# Rocky_Switch_Shield.net
KiCad netlist of a schematic drawn in EAGLE
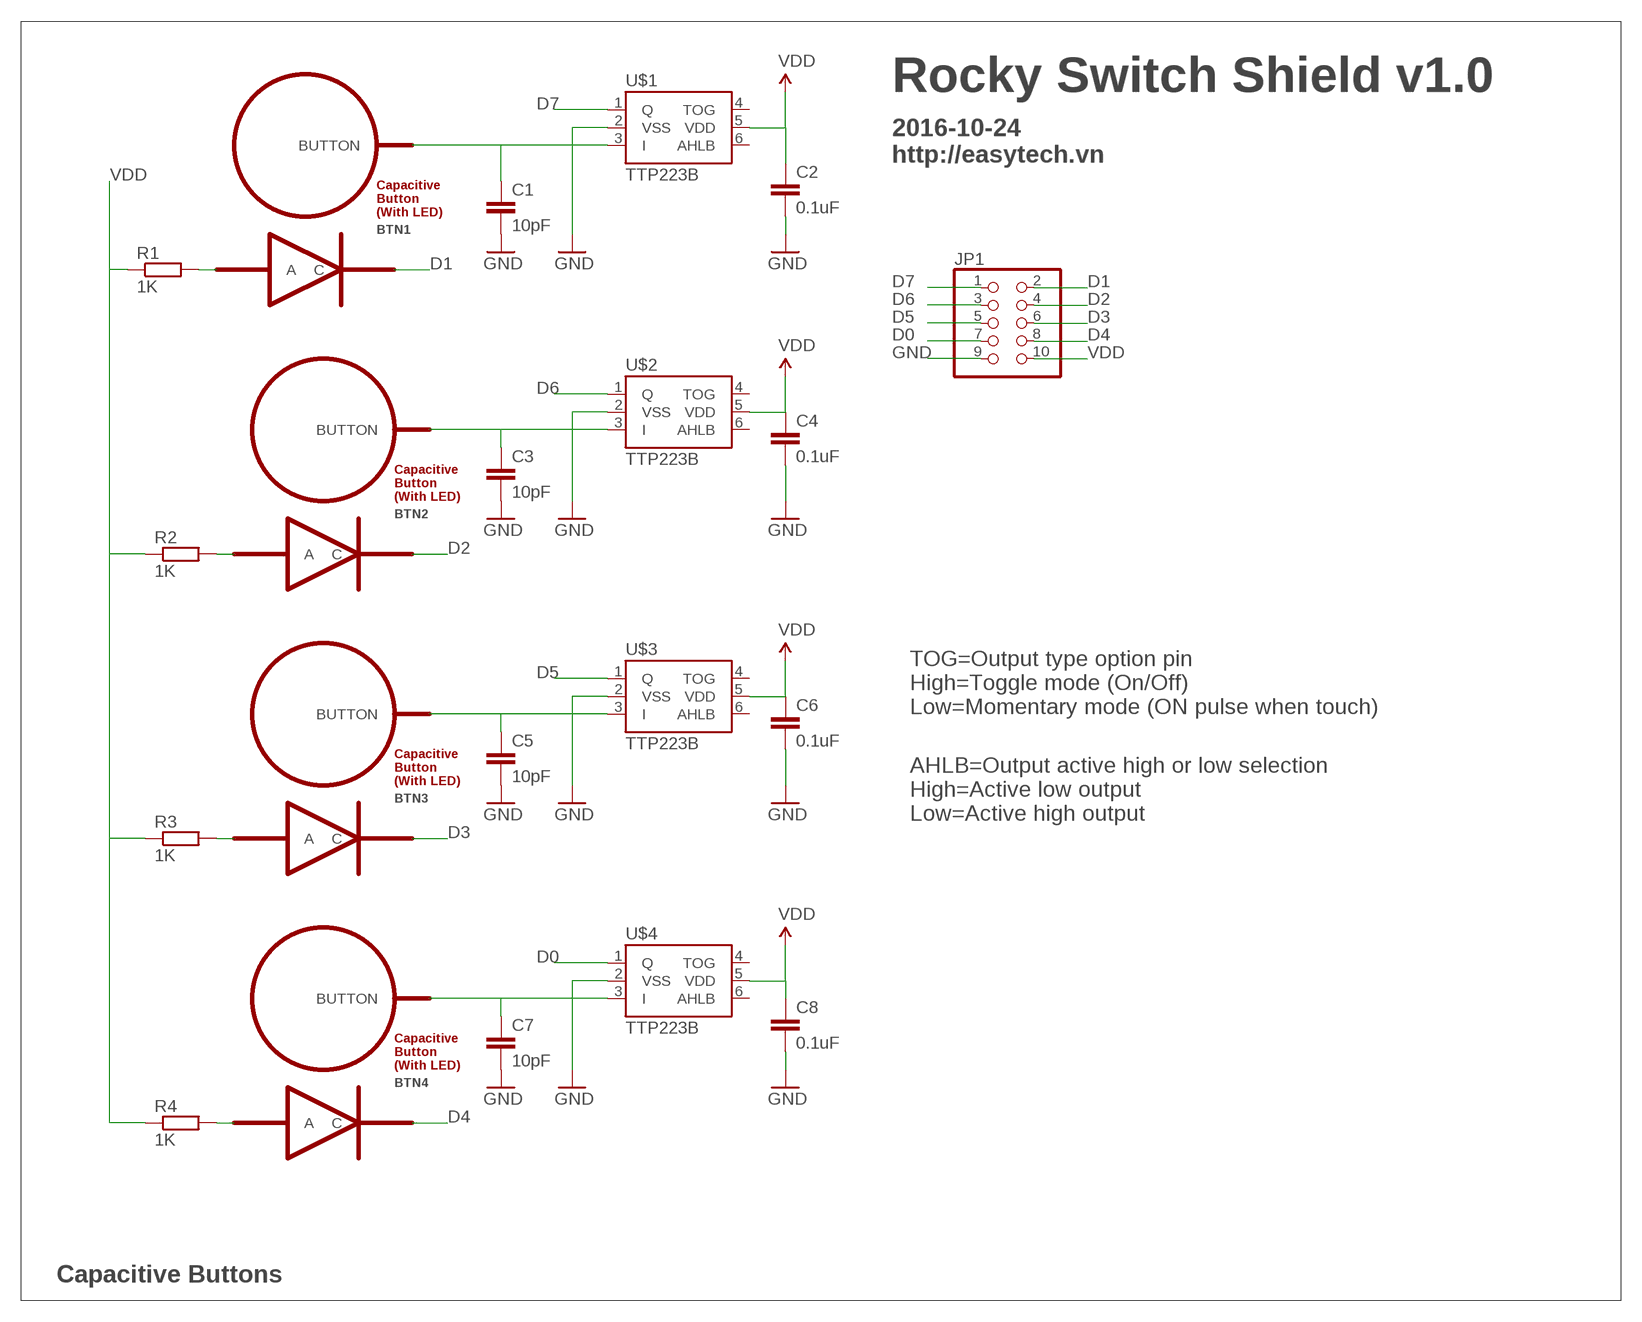
[diagram p0: schematic, sheet 1]

(export (version "E")
  (design (tool "Eeschema 10.0.6"))
  (components
    (comp (ref "BTN1")
      (value "BUTTON_PASSIVE_LED")
      (footprint "eagle-import:BUTTON_PASSIVE_LED")
      (libsource (lib "eagle-import") (part "BUTTON_PASSIVE_LED"))
    )
    (comp (ref "BTN2")
      (value "BUTTON_PASSIVE_LED")
      (footprint "eagle-import:BUTTON_PASSIVE_LED")
      (libsource (lib "eagle-import") (part "BUTTON_PASSIVE_LED"))
    )
    (comp (ref "BTN3")
      (value "BUTTON_PASSIVE_LED")
      (footprint "eagle-import:BUTTON_PASSIVE_LED")
      (libsource (lib "eagle-import") (part "BUTTON_PASSIVE_LED"))
    )
    (comp (ref "BTN4")
      (value "BUTTON_PASSIVE_LED")
      (footprint "eagle-import:BUTTON_PASSIVE_LED")
      (libsource (lib "eagle-import") (part "BUTTON_PASSIVE_LED"))
    )
    (comp (ref "C1")
      (value "10pF")
      (footprint "eagle-import:C0805K")
      (libsource (lib "eagle-import") (part "C-EUC0805K"))
    )
    (comp (ref "C2")
      (value "0.1uF")
      (footprint "eagle-import:C0805K")
      (libsource (lib "eagle-import") (part "C-EUC0805K"))
    )
    (comp (ref "C3")
      (value "10pF")
      (footprint "eagle-import:C0805K")
      (libsource (lib "eagle-import") (part "C-EUC0805K"))
    )
    (comp (ref "C4")
      (value "0.1uF")
      (footprint "eagle-import:C0805K")
      (libsource (lib "eagle-import") (part "C-EUC0805K"))
    )
    (comp (ref "C5")
      (value "10pF")
      (footprint "eagle-import:C0805K")
      (libsource (lib "eagle-import") (part "C-EUC0805K"))
    )
    (comp (ref "C6")
      (value "0.1uF")
      (footprint "eagle-import:C0805K")
      (libsource (lib "eagle-import") (part "C-EUC0805K"))
    )
    (comp (ref "C7")
      (value "10pF")
      (footprint "eagle-import:C0805K")
      (libsource (lib "eagle-import") (part "C-EUC0805K"))
    )
    (comp (ref "C8")
      (value "0.1uF")
      (footprint "eagle-import:C0805K")
      (libsource (lib "eagle-import") (part "C-EUC0805K"))
    )
    (comp (ref "JP1")
      (value "PINHD-2X5")
      (footprint "eagle-import:2X05")
      (libsource (lib "eagle-import") (part "PINHD-2X5"))
    )
    (comp (ref "R1")
      (value "1K")
      (footprint "eagle-import:R0805")
      (libsource (lib "eagle-import") (part "R-EU_R0805"))
    )
    (comp (ref "R2")
      (value "1K")
      (footprint "eagle-import:R0805")
      (libsource (lib "eagle-import") (part "R-EU_R0805"))
    )
    (comp (ref "R3")
      (value "1K")
      (footprint "eagle-import:R0805")
      (libsource (lib "eagle-import") (part "R-EU_R0805"))
    )
    (comp (ref "R4")
      (value "1K")
      (footprint "eagle-import:R0805")
      (libsource (lib "eagle-import") (part "R-EU_R0805"))
    )
    (comp (ref "U$1")
      (value "TTP223B")
      (footprint "eagle-import:SOT23-6")
      (libsource (lib "eagle-import") (part "TTP223B"))
    )
    (comp (ref "U$2")
      (value "TTP223B")
      (footprint "eagle-import:SOT23-6")
      (libsource (lib "eagle-import") (part "TTP223B"))
    )
    (comp (ref "U$3")
      (value "TTP223B")
      (footprint "eagle-import:SOT23-6")
      (libsource (lib "eagle-import") (part "TTP223B"))
    )
    (comp (ref "U$4")
      (value "TTP223B")
      (footprint "eagle-import:SOT23-6")
      (libsource (lib "eagle-import") (part "TTP223B"))
    )
  )
  (nets
    (net (code "1") (name "/D0") (class "Default")
      (node (ref "JP1") (pin "7") (pinfunction "7_7") (pintype "passive"))
      (node (ref "U$4") (pin "1") (pinfunction "Q_1") (pintype "bidirectional"))
    )
    (net (code "2") (name "/D1") (class "Default")
      (node (ref "BTN1") (pin "C") (pinfunction "C_C") (pintype "bidirectional"))
      (node (ref "JP1") (pin "2") (pinfunction "2_2") (pintype "passive"))
    )
    (net (code "3") (name "/D2") (class "Default")
      (node (ref "BTN2") (pin "C") (pinfunction "C_C") (pintype "bidirectional"))
      (node (ref "JP1") (pin "4") (pinfunction "4_4") (pintype "passive"))
    )
    (net (code "4") (name "/D3") (class "Default")
      (node (ref "BTN3") (pin "C") (pinfunction "C_C") (pintype "bidirectional"))
      (node (ref "JP1") (pin "6") (pinfunction "6_6") (pintype "passive"))
    )
    (net (code "5") (name "/D4") (class "Default")
      (node (ref "BTN4") (pin "C") (pinfunction "C_C") (pintype "bidirectional"))
      (node (ref "JP1") (pin "8") (pinfunction "8_8") (pintype "passive"))
    )
    (net (code "6") (name "/D5") (class "Default")
      (node (ref "JP1") (pin "5") (pinfunction "5_5") (pintype "passive"))
      (node (ref "U$3") (pin "1") (pinfunction "Q_1") (pintype "bidirectional"))
    )
    (net (code "7") (name "/D6") (class "Default")
      (node (ref "JP1") (pin "3") (pinfunction "3_3") (pintype "passive"))
      (node (ref "U$2") (pin "1") (pinfunction "Q_1") (pintype "bidirectional"))
    )
    (net (code "8") (name "/D7") (class "Default")
      (node (ref "JP1") (pin "1") (pinfunction "1_1") (pintype "passive"))
      (node (ref "U$1") (pin "1") (pinfunction "Q_1") (pintype "bidirectional"))
    )
    (net (code "9") (name "GND") (class "Default")
      (node (ref "C1") (pin "2") (pinfunction "2_2") (pintype "passive"))
      (node (ref "C2") (pin "2") (pinfunction "2_2") (pintype "passive"))
      (node (ref "C3") (pin "2") (pinfunction "2_2") (pintype "passive"))
      (node (ref "C4") (pin "2") (pinfunction "2_2") (pintype "passive"))
      (node (ref "C5") (pin "2") (pinfunction "2_2") (pintype "passive"))
      (node (ref "C6") (pin "2") (pinfunction "2_2") (pintype "passive"))
      (node (ref "C7") (pin "2") (pinfunction "2_2") (pintype "passive"))
      (node (ref "C8") (pin "2") (pinfunction "2_2") (pintype "passive"))
      (node (ref "JP1") (pin "9") (pinfunction "9_9") (pintype "passive"))
      (node (ref "U$1") (pin "2") (pinfunction "VSS_2") (pintype "bidirectional"))
      (node (ref "U$2") (pin "2") (pinfunction "VSS_2") (pintype "bidirectional"))
      (node (ref "U$3") (pin "2") (pinfunction "VSS_2") (pintype "bidirectional"))
      (node (ref "U$4") (pin "2") (pinfunction "VSS_2") (pintype "bidirectional"))
    )
    (net (code "10") (name "Net-(BTN1-PadA)") (class "Default")
      (node (ref "BTN1") (pin "A") (pinfunction "A_A") (pintype "bidirectional"))
      (node (ref "R1") (pin "2") (pinfunction "2_2") (pintype "passive"))
    )
    (net (code "11") (name "Net-(BTN2-PadA)") (class "Default")
      (node (ref "BTN2") (pin "A") (pinfunction "A_A") (pintype "bidirectional"))
      (node (ref "R2") (pin "2") (pinfunction "2_2") (pintype "passive"))
    )
    (net (code "12") (name "Net-(BTN3-PadA)") (class "Default")
      (node (ref "BTN3") (pin "A") (pinfunction "A_A") (pintype "bidirectional"))
      (node (ref "R3") (pin "2") (pinfunction "2_2") (pintype "passive"))
    )
    (net (code "13") (name "Net-(BTN4-PadA)") (class "Default")
      (node (ref "BTN4") (pin "A") (pinfunction "A_A") (pintype "bidirectional"))
      (node (ref "R4") (pin "2") (pinfunction "2_2") (pintype "passive"))
    )
    (net (code "14") (name "Net-(U$1-I)") (class "Default")
      (node (ref "BTN1") (pin "BUTTON") (pinfunction "BUTTON_BUTTON") (pintype "passive"))
      (node (ref "C1") (pin "1") (pinfunction "1_1") (pintype "passive"))
      (node (ref "U$1") (pin "3") (pinfunction "I_3") (pintype "bidirectional"))
    )
    (net (code "15") (name "Net-(U$2-I)") (class "Default")
      (node (ref "BTN2") (pin "BUTTON") (pinfunction "BUTTON_BUTTON") (pintype "passive"))
      (node (ref "C3") (pin "1") (pinfunction "1_1") (pintype "passive"))
      (node (ref "U$2") (pin "3") (pinfunction "I_3") (pintype "bidirectional"))
    )
    (net (code "16") (name "Net-(U$3-I)") (class "Default")
      (node (ref "BTN3") (pin "BUTTON") (pinfunction "BUTTON_BUTTON") (pintype "passive"))
      (node (ref "C5") (pin "1") (pinfunction "1_1") (pintype "passive"))
      (node (ref "U$3") (pin "3") (pinfunction "I_3") (pintype "bidirectional"))
    )
    (net (code "17") (name "Net-(U$4-I)") (class "Default")
      (node (ref "BTN4") (pin "BUTTON") (pinfunction "BUTTON_BUTTON") (pintype "passive"))
      (node (ref "C7") (pin "1") (pinfunction "1_1") (pintype "passive"))
      (node (ref "U$4") (pin "3") (pinfunction "I_3") (pintype "bidirectional"))
    )
    (net (code "18") (name "VDD") (class "Default")
      (node (ref "C2") (pin "1") (pinfunction "1_1") (pintype "passive"))
      (node (ref "C4") (pin "1") (pinfunction "1_1") (pintype "passive"))
      (node (ref "C6") (pin "1") (pinfunction "1_1") (pintype "passive"))
      (node (ref "C8") (pin "1") (pinfunction "1_1") (pintype "passive"))
      (node (ref "JP1") (pin "10") (pinfunction "10_10") (pintype "passive"))
      (node (ref "R1") (pin "1") (pinfunction "1_1") (pintype "passive"))
      (node (ref "R2") (pin "1") (pinfunction "1_1") (pintype "passive"))
      (node (ref "R3") (pin "1") (pinfunction "1_1") (pintype "passive"))
      (node (ref "R4") (pin "1") (pinfunction "1_1") (pintype "passive"))
      (node (ref "U$1") (pin "5") (pinfunction "VDD_5") (pintype "bidirectional"))
      (node (ref "U$2") (pin "5") (pinfunction "VDD_5") (pintype "bidirectional"))
      (node (ref "U$3") (pin "5") (pinfunction "VDD_5") (pintype "bidirectional"))
      (node (ref "U$4") (pin "5") (pinfunction "VDD_5") (pintype "bidirectional"))
    )
    (net (code "19") (name "unconnected-(U$1-AHLB-Pad6)") (class "Default")
      (node (ref "U$1") (pin "6") (pinfunction "AHLB_6") (pintype "bidirectional"))
    )
    (net (code "20") (name "unconnected-(U$1-TOG-Pad4)") (class "Default")
      (node (ref "U$1") (pin "4") (pinfunction "TOG_4") (pintype "bidirectional"))
    )
    (net (code "21") (name "unconnected-(U$2-AHLB-Pad6)") (class "Default")
      (node (ref "U$2") (pin "6") (pinfunction "AHLB_6") (pintype "bidirectional"))
    )
    (net (code "22") (name "unconnected-(U$2-TOG-Pad4)") (class "Default")
      (node (ref "U$2") (pin "4") (pinfunction "TOG_4") (pintype "bidirectional"))
    )
    (net (code "23") (name "unconnected-(U$3-AHLB-Pad6)") (class "Default")
      (node (ref "U$3") (pin "6") (pinfunction "AHLB_6") (pintype "bidirectional"))
    )
    (net (code "24") (name "unconnected-(U$3-TOG-Pad4)") (class "Default")
      (node (ref "U$3") (pin "4") (pinfunction "TOG_4") (pintype "bidirectional"))
    )
    (net (code "25") (name "unconnected-(U$4-AHLB-Pad6)") (class "Default")
      (node (ref "U$4") (pin "6") (pinfunction "AHLB_6") (pintype "bidirectional"))
    )
    (net (code "26") (name "unconnected-(U$4-TOG-Pad4)") (class "Default")
      (node (ref "U$4") (pin "4") (pinfunction "TOG_4") (pintype "bidirectional"))
    )
  )
)
